# 9_LPDDR4_SDRAM1.net
KiCad netlist of a schematic drawn in Altium Designer
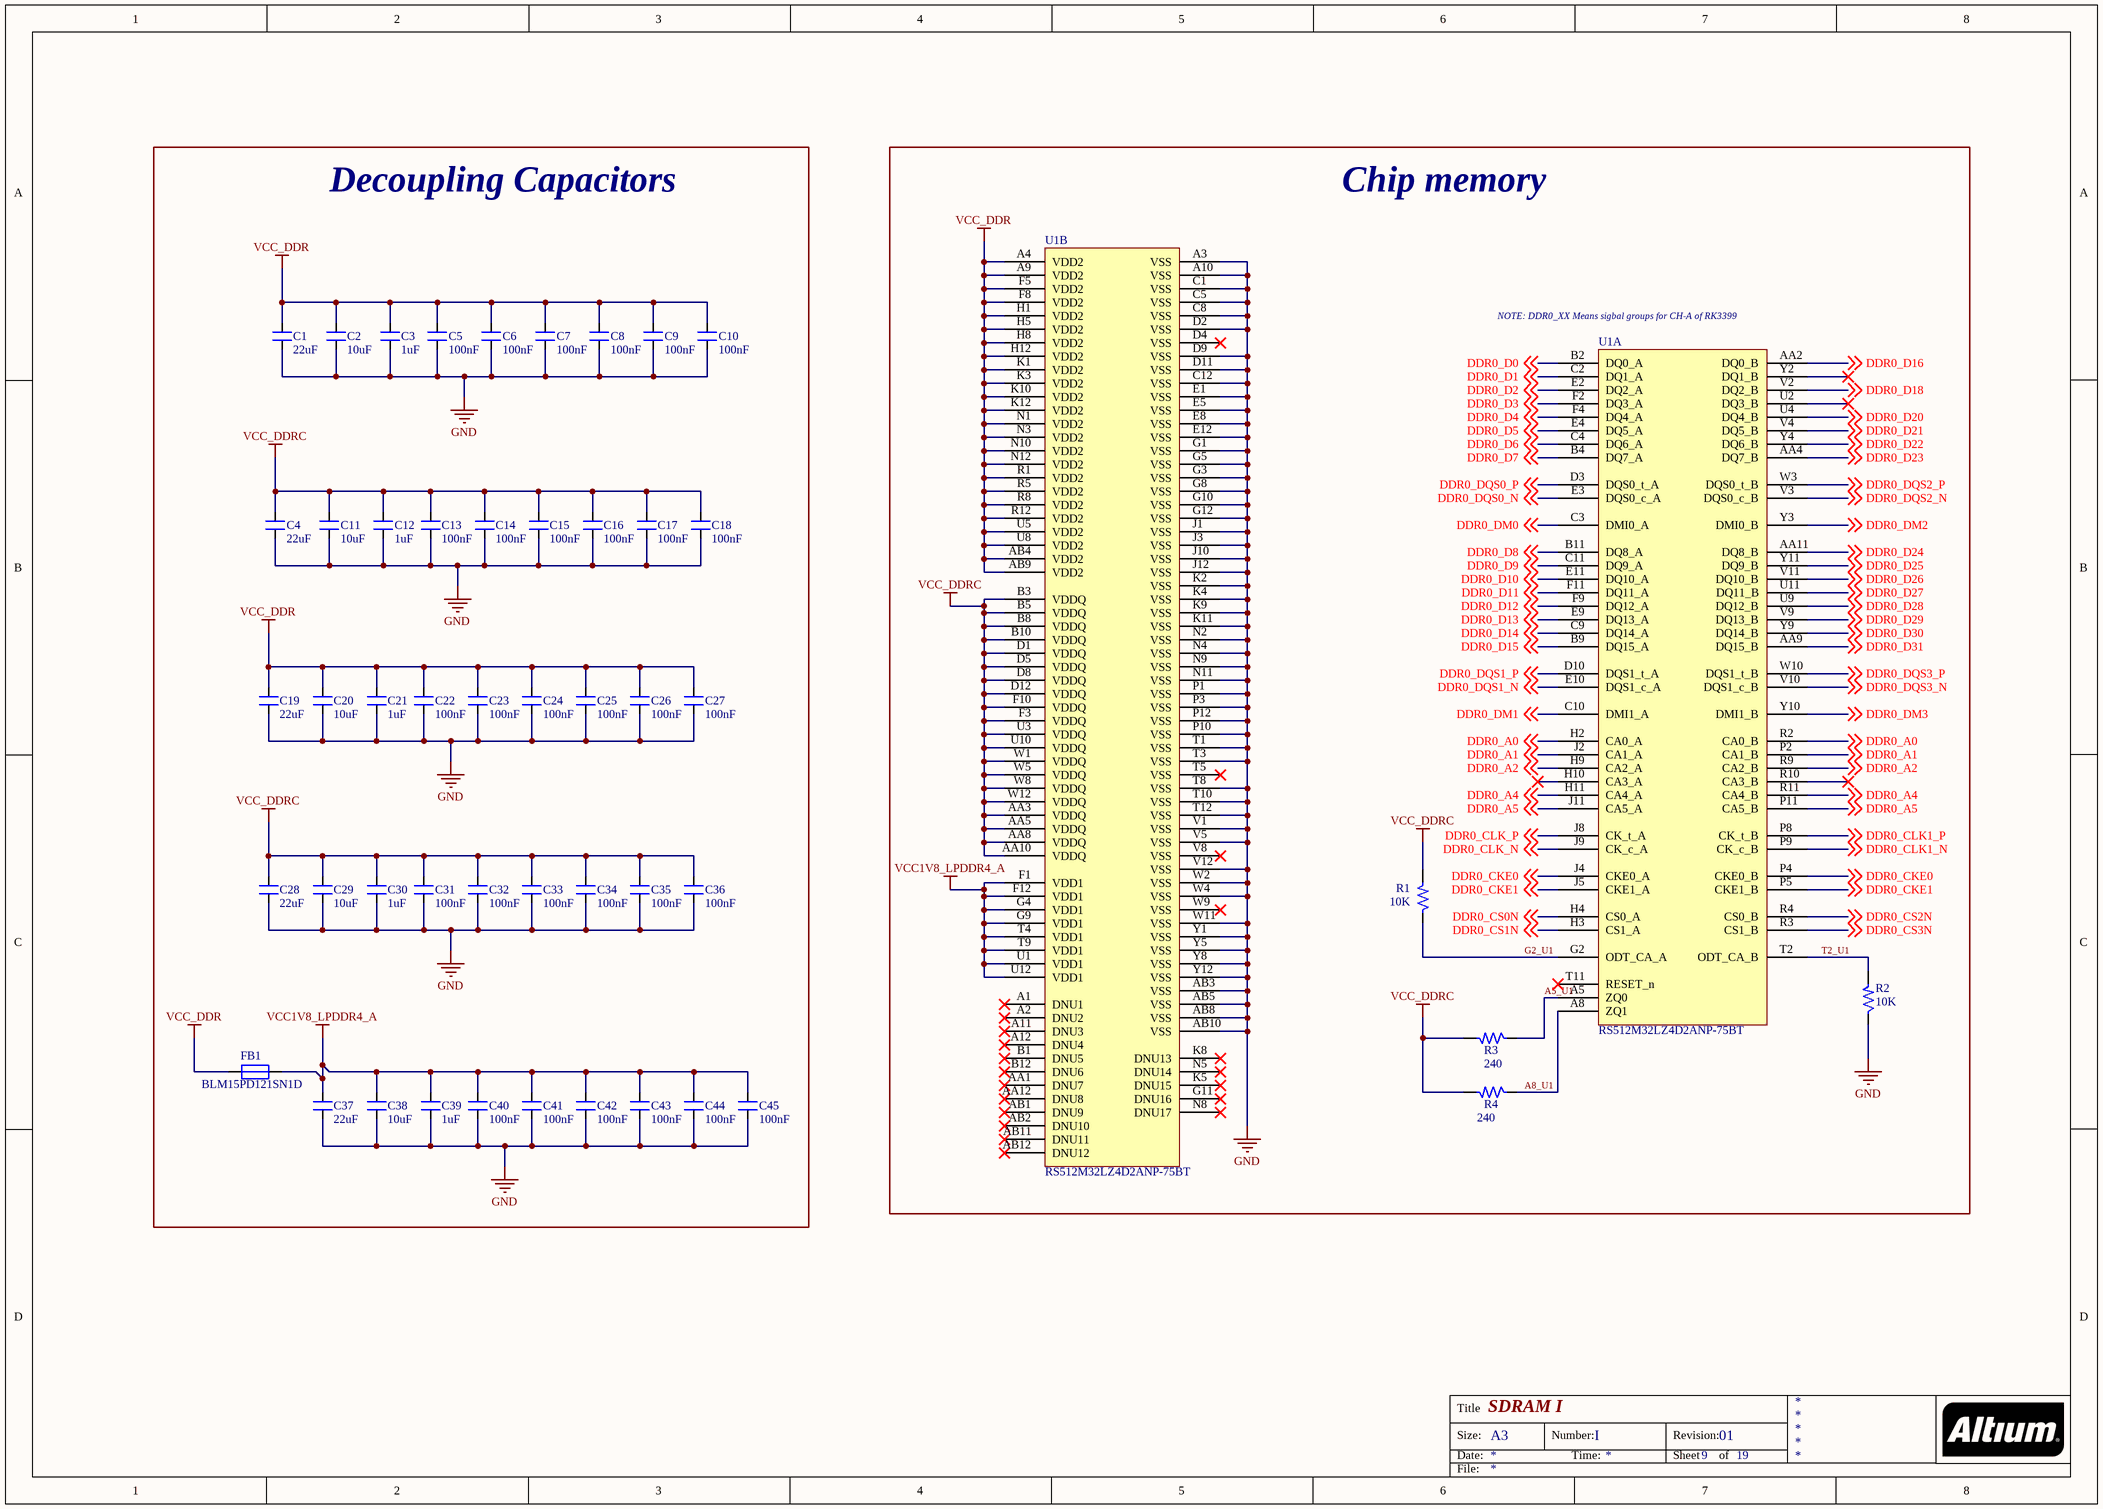
[diagram p0: [9] LPDDR4_SDRAM1.SchDoc]

(export (version "E")
  (design (tool "Eeschema 10.0.6"))
  (components
    (comp (ref "C1")
      (value "22uF")
      (footprint "CAP_0402")
      (description "22µF ±20% 6.3V Ceramic Capacitor X5R 0402 (1005 Metric)")
      (fields
        (field (name "MANUFACTURER") "Murata Electronics")
        (field (name "MANUFACTURER PART NUMBER") "CL05A226MQ5N6J8")
      )
      (libsource (lib "EsteemPCB_SOM_Course_intlib") (part "CAP_22uF-6.3V-20%-0402"))
    )
    (comp (ref "C2")
      (value "10uF")
      (footprint "CAP_0402")
      (description "10µF ±20% 10V Ceramic Capacitor X5R 0402 (1005 Metric)")
      (fields
        (field (name "MANUFACTURER PART NUMBER") "CL05A106MP5NUNC")
        (field (name "MANUFACTURER") "Samsung Electro-Mechanics")
      )
      (libsource (lib "EsteemPCB_SOM_Course_intlib") (part "CAP_10uF-10V-20%-0402"))
    )
    (comp (ref "C3")
      (value "1uF")
      (footprint "CAP_0201")
      (description "1µF ±20% 16V Ceramic Capacitor X5R 0201 (0603 Metric)")
      (fields
        (field (name "MANUFACTURER") "Samsung Electro-Mechanics")
        (field (name "MANUFACTURER PART NUMBER") "CL03A105MO3NRNH")
      )
      (libsource (lib "EsteemPCB_SOM_Course_intlib") (part "CAP_1uF-16V-10%-0201"))
    )
    (comp (ref "C4")
      (value "22uF")
      (footprint "CAP_0402")
      (description "22µF ±20% 6.3V Ceramic Capacitor X5R 0402 (1005 Metric)")
      (fields
        (field (name "MANUFACTURER") "Murata Electronics")
        (field (name "MANUFACTURER PART NUMBER") "CL05A226MQ5N6J8")
      )
      (libsource (lib "EsteemPCB_SOM_Course_intlib") (part "CAP_22uF-6.3V-20%-0402"))
    )
    (comp (ref "C5")
      (value "100nF")
      (footprint "CAP_0201")
      (description "0.1µF ±10% 25V Ceramic Capacitor X5R 0201 (0603 Metric)")
      (fields
        (field (name "MANUFACTURER") "TDK Corporation")
        (field (name "MANUFACTURER PART NUMBER") "C0603X5R1E104K030BB")
      )
      (libsource (lib "EsteemPCB_SOM_Course_intlib") (part "CAP_100nF-25V-10%-0201"))
    )
    (comp (ref "C6")
      (value "100nF")
      (footprint "CAP_0201")
      (description "0.1µF ±10% 25V Ceramic Capacitor X5R 0201 (0603 Metric)")
      (fields
        (field (name "MANUFACTURER") "TDK Corporation")
        (field (name "MANUFACTURER PART NUMBER") "C0603X5R1E104K030BB")
      )
      (libsource (lib "EsteemPCB_SOM_Course_intlib") (part "CAP_100nF-25V-10%-0201"))
    )
    (comp (ref "C7")
      (value "100nF")
      (footprint "CAP_0201")
      (description "0.1µF ±10% 25V Ceramic Capacitor X5R 0201 (0603 Metric)")
      (fields
        (field (name "MANUFACTURER") "TDK Corporation")
        (field (name "MANUFACTURER PART NUMBER") "C0603X5R1E104K030BB")
      )
      (libsource (lib "EsteemPCB_SOM_Course_intlib") (part "CAP_100nF-25V-10%-0201"))
    )
    (comp (ref "C8")
      (value "100nF")
      (footprint "CAP_0201")
      (description "0.1µF ±10% 25V Ceramic Capacitor X5R 0201 (0603 Metric)")
      (fields
        (field (name "MANUFACTURER") "TDK Corporation")
        (field (name "MANUFACTURER PART NUMBER") "C0603X5R1E104K030BB")
      )
      (libsource (lib "EsteemPCB_SOM_Course_intlib") (part "CAP_100nF-25V-10%-0201"))
    )
    (comp (ref "C9")
      (value "100nF")
      (footprint "CAP_0201")
      (description "0.1µF ±10% 25V Ceramic Capacitor X5R 0201 (0603 Metric)")
      (fields
        (field (name "MANUFACTURER") "TDK Corporation")
        (field (name "MANUFACTURER PART NUMBER") "C0603X5R1E104K030BB")
      )
      (libsource (lib "EsteemPCB_SOM_Course_intlib") (part "CAP_100nF-25V-10%-0201"))
    )
    (comp (ref "C10")
      (value "100nF")
      (footprint "CAP_0201")
      (description "0.1µF ±10% 25V Ceramic Capacitor X5R 0201 (0603 Metric)")
      (fields
        (field (name "MANUFACTURER") "TDK Corporation")
        (field (name "MANUFACTURER PART NUMBER") "C0603X5R1E104K030BB")
      )
      (libsource (lib "EsteemPCB_SOM_Course_intlib") (part "CAP_100nF-25V-10%-0201"))
    )
    (comp (ref "C11")
      (value "10uF")
      (footprint "CAP_0402")
      (description "10µF ±20% 10V Ceramic Capacitor X5R 0402 (1005 Metric)")
      (fields
        (field (name "MANUFACTURER PART NUMBER") "CL05A106MP5NUNC")
        (field (name "MANUFACTURER") "Samsung Electro-Mechanics")
      )
      (libsource (lib "EsteemPCB_SOM_Course_intlib") (part "CAP_10uF-10V-20%-0402"))
    )
    (comp (ref "C12")
      (value "1uF")
      (footprint "CAP_0201")
      (description "1µF ±20% 16V Ceramic Capacitor X5R 0201 (0603 Metric)")
      (fields
        (field (name "MANUFACTURER") "Samsung Electro-Mechanics")
        (field (name "MANUFACTURER PART NUMBER") "CL03A105MO3NRNH")
      )
      (libsource (lib "EsteemPCB_SOM_Course_intlib") (part "CAP_1uF-16V-10%-0201"))
    )
    (comp (ref "C13")
      (value "100nF")
      (footprint "CAP_0201")
      (description "0.1µF ±10% 25V Ceramic Capacitor X5R 0201 (0603 Metric)")
      (fields
        (field (name "MANUFACTURER") "TDK Corporation")
        (field (name "MANUFACTURER PART NUMBER") "C0603X5R1E104K030BB")
      )
      (libsource (lib "EsteemPCB_SOM_Course_intlib") (part "CAP_100nF-25V-10%-0201"))
    )
    (comp (ref "C14")
      (value "100nF")
      (footprint "CAP_0201")
      (description "0.1µF ±10% 25V Ceramic Capacitor X5R 0201 (0603 Metric)")
      (fields
        (field (name "MANUFACTURER") "TDK Corporation")
        (field (name "MANUFACTURER PART NUMBER") "C0603X5R1E104K030BB")
      )
      (libsource (lib "EsteemPCB_SOM_Course_intlib") (part "CAP_100nF-25V-10%-0201"))
    )
    (comp (ref "C15")
      (value "100nF")
      (footprint "CAP_0201")
      (description "0.1µF ±10% 25V Ceramic Capacitor X5R 0201 (0603 Metric)")
      (fields
        (field (name "MANUFACTURER") "TDK Corporation")
        (field (name "MANUFACTURER PART NUMBER") "C0603X5R1E104K030BB")
      )
      (libsource (lib "EsteemPCB_SOM_Course_intlib") (part "CAP_100nF-25V-10%-0201"))
    )
    (comp (ref "C16")
      (value "100nF")
      (footprint "CAP_0201")
      (description "0.1µF ±10% 25V Ceramic Capacitor X5R 0201 (0603 Metric)")
      (fields
        (field (name "MANUFACTURER") "TDK Corporation")
        (field (name "MANUFACTURER PART NUMBER") "C0603X5R1E104K030BB")
      )
      (libsource (lib "EsteemPCB_SOM_Course_intlib") (part "CAP_100nF-25V-10%-0201"))
    )
    (comp (ref "C17")
      (value "100nF")
      (footprint "CAP_0201")
      (description "0.1µF ±10% 25V Ceramic Capacitor X5R 0201 (0603 Metric)")
      (fields
        (field (name "MANUFACTURER") "TDK Corporation")
        (field (name "MANUFACTURER PART NUMBER") "C0603X5R1E104K030BB")
      )
      (libsource (lib "EsteemPCB_SOM_Course_intlib") (part "CAP_100nF-25V-10%-0201"))
    )
    (comp (ref "C18")
      (value "100nF")
      (footprint "CAP_0201")
      (description "0.1µF ±10% 25V Ceramic Capacitor X5R 0201 (0603 Metric)")
      (fields
        (field (name "MANUFACTURER") "TDK Corporation")
        (field (name "MANUFACTURER PART NUMBER") "C0603X5R1E104K030BB")
      )
      (libsource (lib "EsteemPCB_SOM_Course_intlib") (part "CAP_100nF-25V-10%-0201"))
    )
    (comp (ref "C19")
      (value "22uF")
      (footprint "CAP_0402")
      (description "22µF ±20% 6.3V Ceramic Capacitor X5R 0402 (1005 Metric)")
      (fields
        (field (name "MANUFACTURER") "Murata Electronics")
        (field (name "MANUFACTURER PART NUMBER") "CL05A226MQ5N6J8")
      )
      (libsource (lib "EsteemPCB_SOM_Course_intlib") (part "CAP_22uF-6.3V-20%-0402"))
    )
    (comp (ref "C20")
      (value "10uF")
      (footprint "CAP_0402")
      (description "10µF ±20% 10V Ceramic Capacitor X5R 0402 (1005 Metric)")
      (fields
        (field (name "MANUFACTURER PART NUMBER") "CL05A106MP5NUNC")
        (field (name "MANUFACTURER") "Samsung Electro-Mechanics")
      )
      (libsource (lib "EsteemPCB_SOM_Course_intlib") (part "CAP_10uF-10V-20%-0402"))
    )
    (comp (ref "C21")
      (value "1uF")
      (footprint "CAP_0201")
      (description "1µF ±20% 16V Ceramic Capacitor X5R 0201 (0603 Metric)")
      (fields
        (field (name "MANUFACTURER") "Samsung Electro-Mechanics")
        (field (name "MANUFACTURER PART NUMBER") "CL03A105MO3NRNH")
      )
      (libsource (lib "EsteemPCB_SOM_Course_intlib") (part "CAP_1uF-16V-10%-0201"))
    )
    (comp (ref "C22")
      (value "100nF")
      (footprint "CAP_0201")
      (description "0.1µF ±10% 25V Ceramic Capacitor X5R 0201 (0603 Metric)")
      (fields
        (field (name "MANUFACTURER") "TDK Corporation")
        (field (name "MANUFACTURER PART NUMBER") "C0603X5R1E104K030BB")
      )
      (libsource (lib "EsteemPCB_SOM_Course_intlib") (part "CAP_100nF-25V-10%-0201"))
    )
    (comp (ref "C23")
      (value "100nF")
      (footprint "CAP_0201")
      (description "0.1µF ±10% 25V Ceramic Capacitor X5R 0201 (0603 Metric)")
      (fields
        (field (name "MANUFACTURER") "TDK Corporation")
        (field (name "MANUFACTURER PART NUMBER") "C0603X5R1E104K030BB")
      )
      (libsource (lib "EsteemPCB_SOM_Course_intlib") (part "CAP_100nF-25V-10%-0201"))
    )
    (comp (ref "C24")
      (value "100nF")
      (footprint "CAP_0201")
      (description "0.1µF ±10% 25V Ceramic Capacitor X5R 0201 (0603 Metric)")
      (fields
        (field (name "MANUFACTURER") "TDK Corporation")
        (field (name "MANUFACTURER PART NUMBER") "C0603X5R1E104K030BB")
      )
      (libsource (lib "EsteemPCB_SOM_Course_intlib") (part "CAP_100nF-25V-10%-0201"))
    )
    (comp (ref "C25")
      (value "100nF")
      (footprint "CAP_0201")
      (description "0.1µF ±10% 25V Ceramic Capacitor X5R 0201 (0603 Metric)")
      (fields
        (field (name "MANUFACTURER") "TDK Corporation")
        (field (name "MANUFACTURER PART NUMBER") "C0603X5R1E104K030BB")
      )
      (libsource (lib "EsteemPCB_SOM_Course_intlib") (part "CAP_100nF-25V-10%-0201"))
    )
    (comp (ref "C26")
      (value "100nF")
      (footprint "CAP_0201")
      (description "0.1µF ±10% 25V Ceramic Capacitor X5R 0201 (0603 Metric)")
      (fields
        (field (name "MANUFACTURER") "TDK Corporation")
        (field (name "MANUFACTURER PART NUMBER") "C0603X5R1E104K030BB")
      )
      (libsource (lib "EsteemPCB_SOM_Course_intlib") (part "CAP_100nF-25V-10%-0201"))
    )
    (comp (ref "C27")
      (value "100nF")
      (footprint "CAP_0201")
      (description "0.1µF ±10% 25V Ceramic Capacitor X5R 0201 (0603 Metric)")
      (fields
        (field (name "MANUFACTURER") "TDK Corporation")
        (field (name "MANUFACTURER PART NUMBER") "C0603X5R1E104K030BB")
      )
      (libsource (lib "EsteemPCB_SOM_Course_intlib") (part "CAP_100nF-25V-10%-0201"))
    )
    (comp (ref "C28")
      (value "22uF")
      (footprint "CAP_0402")
      (description "22µF ±20% 6.3V Ceramic Capacitor X5R 0402 (1005 Metric)")
      (fields
        (field (name "MANUFACTURER") "Murata Electronics")
        (field (name "MANUFACTURER PART NUMBER") "CL05A226MQ5N6J8")
      )
      (libsource (lib "EsteemPCB_SOM_Course_intlib") (part "CAP_22uF-6.3V-20%-0402"))
    )
    (comp (ref "C29")
      (value "10uF")
      (footprint "CAP_0402")
      (description "10µF ±20% 10V Ceramic Capacitor X5R 0402 (1005 Metric)")
      (fields
        (field (name "MANUFACTURER PART NUMBER") "CL05A106MP5NUNC")
        (field (name "MANUFACTURER") "Samsung Electro-Mechanics")
      )
      (libsource (lib "EsteemPCB_SOM_Course_intlib") (part "CAP_10uF-10V-20%-0402"))
    )
    (comp (ref "C30")
      (value "1uF")
      (footprint "CAP_0201")
      (description "1µF ±20% 16V Ceramic Capacitor X5R 0201 (0603 Metric)")
      (fields
        (field (name "MANUFACTURER") "Samsung Electro-Mechanics")
        (field (name "MANUFACTURER PART NUMBER") "CL03A105MO3NRNH")
      )
      (libsource (lib "EsteemPCB_SOM_Course_intlib") (part "CAP_1uF-16V-10%-0201"))
    )
    (comp (ref "C31")
      (value "100nF")
      (footprint "CAP_0201")
      (description "0.1µF ±10% 25V Ceramic Capacitor X5R 0201 (0603 Metric)")
      (fields
        (field (name "MANUFACTURER") "TDK Corporation")
        (field (name "MANUFACTURER PART NUMBER") "C0603X5R1E104K030BB")
      )
      (libsource (lib "EsteemPCB_SOM_Course_intlib") (part "CAP_100nF-25V-10%-0201"))
    )
    (comp (ref "C32")
      (value "100nF")
      (footprint "CAP_0201")
      (description "0.1µF ±10% 25V Ceramic Capacitor X5R 0201 (0603 Metric)")
      (fields
        (field (name "MANUFACTURER") "TDK Corporation")
        (field (name "MANUFACTURER PART NUMBER") "C0603X5R1E104K030BB")
      )
      (libsource (lib "EsteemPCB_SOM_Course_intlib") (part "CAP_100nF-25V-10%-0201"))
    )
    (comp (ref "C33")
      (value "100nF")
      (footprint "CAP_0201")
      (description "0.1µF ±10% 25V Ceramic Capacitor X5R 0201 (0603 Metric)")
      (fields
        (field (name "MANUFACTURER") "TDK Corporation")
        (field (name "MANUFACTURER PART NUMBER") "C0603X5R1E104K030BB")
      )
      (libsource (lib "EsteemPCB_SOM_Course_intlib") (part "CAP_100nF-25V-10%-0201"))
    )
    (comp (ref "C34")
      (value "100nF")
      (footprint "CAP_0201")
      (description "0.1µF ±10% 25V Ceramic Capacitor X5R 0201 (0603 Metric)")
      (fields
        (field (name "MANUFACTURER") "TDK Corporation")
        (field (name "MANUFACTURER PART NUMBER") "C0603X5R1E104K030BB")
      )
      (libsource (lib "EsteemPCB_SOM_Course_intlib") (part "CAP_100nF-25V-10%-0201"))
    )
    (comp (ref "C35")
      (value "100nF")
      (footprint "CAP_0201")
      (description "0.1µF ±10% 25V Ceramic Capacitor X5R 0201 (0603 Metric)")
      (fields
        (field (name "MANUFACTURER") "TDK Corporation")
        (field (name "MANUFACTURER PART NUMBER") "C0603X5R1E104K030BB")
      )
      (libsource (lib "EsteemPCB_SOM_Course_intlib") (part "CAP_100nF-25V-10%-0201"))
    )
    (comp (ref "C36")
      (value "100nF")
      (footprint "CAP_0201")
      (description "0.1µF ±10% 25V Ceramic Capacitor X5R 0201 (0603 Metric)")
      (fields
        (field (name "MANUFACTURER") "TDK Corporation")
        (field (name "MANUFACTURER PART NUMBER") "C0603X5R1E104K030BB")
      )
      (libsource (lib "EsteemPCB_SOM_Course_intlib") (part "CAP_100nF-25V-10%-0201"))
    )
    (comp (ref "C37")
      (value "22uF")
      (footprint "CAP_0402")
      (description "22µF ±20% 6.3V Ceramic Capacitor X5R 0402 (1005 Metric)")
      (fields
        (field (name "MANUFACTURER") "Murata Electronics")
        (field (name "MANUFACTURER PART NUMBER") "CL05A226MQ5N6J8")
      )
      (libsource (lib "EsteemPCB_SOM_Course_intlib") (part "CAP_22uF-6.3V-20%-0402"))
    )
    (comp (ref "C38")
      (value "10uF")
      (footprint "CAP_0402")
      (description "10µF ±20% 10V Ceramic Capacitor X5R 0402 (1005 Metric)")
      (fields
        (field (name "MANUFACTURER PART NUMBER") "CL05A106MP5NUNC")
        (field (name "MANUFACTURER") "Samsung Electro-Mechanics")
      )
      (libsource (lib "EsteemPCB_SOM_Course_intlib") (part "CAP_10uF-10V-20%-0402"))
    )
    (comp (ref "C39")
      (value "1uF")
      (footprint "CAP_0201")
      (description "1µF ±20% 16V Ceramic Capacitor X5R 0201 (0603 Metric)")
      (fields
        (field (name "MANUFACTURER") "Samsung Electro-Mechanics")
        (field (name "MANUFACTURER PART NUMBER") "CL03A105MO3NRNH")
      )
      (libsource (lib "EsteemPCB_SOM_Course_intlib") (part "CAP_1uF-16V-10%-0201"))
    )
    (comp (ref "C40")
      (value "100nF")
      (footprint "CAP_0201")
      (description "0.1µF ±10% 25V Ceramic Capacitor X5R 0201 (0603 Metric)")
      (fields
        (field (name "MANUFACTURER") "TDK Corporation")
        (field (name "MANUFACTURER PART NUMBER") "C0603X5R1E104K030BB")
      )
      (libsource (lib "EsteemPCB_SOM_Course_intlib") (part "CAP_100nF-25V-10%-0201"))
    )
    (comp (ref "C41")
      (value "100nF")
      (footprint "CAP_0201")
      (description "0.1µF ±10% 25V Ceramic Capacitor X5R 0201 (0603 Metric)")
      (fields
        (field (name "MANUFACTURER") "TDK Corporation")
        (field (name "MANUFACTURER PART NUMBER") "C0603X5R1E104K030BB")
      )
      (libsource (lib "EsteemPCB_SOM_Course_intlib") (part "CAP_100nF-25V-10%-0201"))
    )
    (comp (ref "C42")
      (value "100nF")
      (footprint "CAP_0201")
      (description "0.1µF ±10% 25V Ceramic Capacitor X5R 0201 (0603 Metric)")
      (fields
        (field (name "MANUFACTURER") "TDK Corporation")
        (field (name "MANUFACTURER PART NUMBER") "C0603X5R1E104K030BB")
      )
      (libsource (lib "EsteemPCB_SOM_Course_intlib") (part "CAP_100nF-25V-10%-0201"))
    )
    (comp (ref "C43")
      (value "100nF")
      (footprint "CAP_0201")
      (description "0.1µF ±10% 25V Ceramic Capacitor X5R 0201 (0603 Metric)")
      (fields
        (field (name "MANUFACTURER") "TDK Corporation")
        (field (name "MANUFACTURER PART NUMBER") "C0603X5R1E104K030BB")
      )
      (libsource (lib "EsteemPCB_SOM_Course_intlib") (part "CAP_100nF-25V-10%-0201"))
    )
    (comp (ref "C44")
      (value "100nF")
      (footprint "CAP_0201")
      (description "0.1µF ±10% 25V Ceramic Capacitor X5R 0201 (0603 Metric)")
      (fields
        (field (name "MANUFACTURER") "TDK Corporation")
        (field (name "MANUFACTURER PART NUMBER") "C0603X5R1E104K030BB")
      )
      (libsource (lib "EsteemPCB_SOM_Course_intlib") (part "CAP_100nF-25V-10%-0201"))
    )
    (comp (ref "C45")
      (value "100nF")
      (footprint "CAP_0201")
      (description "0.1µF ±10% 25V Ceramic Capacitor X5R 0201 (0603 Metric)")
      (fields
        (field (name "MANUFACTURER") "TDK Corporation")
        (field (name "MANUFACTURER PART NUMBER") "C0603X5R1E104K030BB")
      )
      (libsource (lib "EsteemPCB_SOM_Course_intlib") (part "CAP_100nF-25V-10%-0201"))
    )
    (comp (ref "FB1")
      (value "BLM15PD121SN1D")
      (footprint "RES_0402")
      (description "120 Ohms @ 100MHz 1 Power Line Ferrite Bead 0402 (1005 Metric) 1.3A 90mOhm")
      (fields (field (name "MANUFACTURER") "Murata Electronics"))
      (libsource (lib "EsteemPCB_SOM_Course_intlib") (part "FB_120R-1.3A-100Mhz-0402"))
    )
    (comp (ref "R1")
      (value "10K")
      (footprint "RES_0201")
      (description "10 kOhms ±1% 0.05W, 1/20W Chip Resistor 0201 (0603 Metric) Thick Film")
      (fields
        (field (name "MANUFACTURER") "Stackpole Electronics Inc")
        (field (name "MANUFACTURER PART NUMBER") "RMCF0201FT10K0")
      )
      (libsource (lib "EsteemPCB_SOM_Course_intlib") (part "RES_10K-0.05W-1%-0201"))
    )
    (comp (ref "R2")
      (value "10K")
      (footprint "RES_0201")
      (description "10 kOhms ±1% 0.05W, 1/20W Chip Resistor 0201 (0603 Metric) Thick Film")
      (fields
        (field (name "MANUFACTURER") "Stackpole Electronics Inc")
        (field (name "MANUFACTURER PART NUMBER") "RMCF0201FT10K0")
      )
      (libsource (lib "EsteemPCB_SOM_Course_intlib") (part "RES_10K-0.05W-1%-0201"))
    )
    (comp (ref "R3")
      (value "240")
      (footprint "RES_0201")
      (description "10 kOhms ±1% 0.05W, 1/20W Chip Resistor 0201 (0603 Metric) Thick Film")
      (fields
        (field (name "MANUFACTURER") "Stackpole Electronics Inc")
        (field (name "MANUFACTURER PART NUMBER") "RMCF0201FT10K0")
      )
      (libsource (lib "EsteemPCB_SOM_Course_intlib") (part "RES_10K-0.05W-1%-0201"))
    )
    (comp (ref "R4")
      (value "240")
      (footprint "RES_0201")
      (description "10 kOhms ±1% 0.05W, 1/20W Chip Resistor 0201 (0603 Metric) Thick Film")
      (fields
        (field (name "MANUFACTURER") "Stackpole Electronics Inc")
        (field (name "MANUFACTURER PART NUMBER") "RMCF0201FT10K0")
      )
      (libsource (lib "EsteemPCB_SOM_Course_intlib") (part "RES_10K-0.05W-1%-0201"))
    )
    (comp (ref "U1")
      (value "RS512M32LZ4D2ANP-75BT")
      (footprint "FBGA200_SMD")
      (fields (field (name "MANUFACTURER") "RAYSON"))
      (libsource (lib "EsteemPCB_SOM_Course_intlib") (part "IC_RS512M32LZ4D2ANP-75BT"))
    )
  )
  (nets
    (net (code "1") (name "/A5_U1") (class "Default")
      (node (ref "R3") (pin "1") (pinfunction "1_1") (pintype "passive"))
      (node (ref "U1") (pin "A5") (pinfunction "ZQ0_A5") (pintype "passive"))
    )
    (net (code "2") (name "/A8_U1") (class "Default")
      (node (ref "R4") (pin "1") (pinfunction "1_1") (pintype "passive"))
      (node (ref "U1") (pin "A8") (pinfunction "ZQ1_A8") (pintype "passive"))
    )
    (net (code "3") (name "/G2_U1") (class "Default")
      (node (ref "R1") (pin "1") (pinfunction "1_1") (pintype "passive"))
      (node (ref "U1") (pin "G2") (pinfunction "ODT_CA_A_G2") (pintype "passive"))
    )
    (net (code "4") (name "/T2_U1") (class "Default")
      (node (ref "R2") (pin "2") (pinfunction "2_2") (pintype "passive"))
      (node (ref "U1") (pin "T2") (pinfunction "ODT_CA_B_T2") (pintype "passive"))
    )
    (net (code "5") (name "DDR0_A0") (class "Default")
      (node (ref "U1") (pin "H2") (pinfunction "CA0_A_H2") (pintype "passive"))
      (node (ref "U1") (pin "R2") (pinfunction "CA0_B_R2") (pintype "passive"))
    )
    (net (code "6") (name "DDR0_A1") (class "Default")
      (node (ref "U1") (pin "J2") (pinfunction "CA1_A_J2") (pintype "passive"))
      (node (ref "U1") (pin "P2") (pinfunction "CA1_B_P2") (pintype "passive"))
    )
    (net (code "7") (name "DDR0_A2") (class "Default")
      (node (ref "U1") (pin "H9") (pinfunction "CA2_A_H9") (pintype "passive"))
      (node (ref "U1") (pin "R9") (pinfunction "CA2_B_R9") (pintype "passive"))
    )
    (net (code "8") (name "DDR0_A4") (class "Default")
      (node (ref "U1") (pin "H11") (pinfunction "CA4_A_H11") (pintype "passive"))
      (node (ref "U1") (pin "R11") (pinfunction "CA4_B_R11") (pintype "passive"))
    )
    (net (code "9") (name "DDR0_A5") (class "Default")
      (node (ref "U1") (pin "J11") (pinfunction "CA5_A_J11") (pintype "passive"))
      (node (ref "U1") (pin "P11") (pinfunction "CA5_B_P11") (pintype "passive"))
    )
    (net (code "10") (name "DDR0_CKE0") (class "Default")
      (node (ref "U1") (pin "J4") (pinfunction "CKE0_A_J4") (pintype "passive"))
      (node (ref "U1") (pin "P4") (pinfunction "CKE0_B_P4") (pintype "passive"))
    )
    (net (code "11") (name "DDR0_CKE1") (class "Default")
      (node (ref "U1") (pin "J5") (pinfunction "CKE1_A_J5") (pintype "passive"))
      (node (ref "U1") (pin "P5") (pinfunction "CKE1_B_P5") (pintype "passive"))
    )
    (net (code "12") (name "DDR0_CLK1_N") (class "Default")
      (node (ref "U1") (pin "P9") (pinfunction "CK_c_B_P9") (pintype "passive"))
    )
    (net (code "13") (name "DDR0_CLK1_P") (class "Default")
      (node (ref "U1") (pin "P8") (pinfunction "CK_t_B_P8") (pintype "passive"))
    )
    (net (code "14") (name "DDR0_CLK_N") (class "Default")
      (node (ref "U1") (pin "J9") (pinfunction "CK_c_A_J9") (pintype "passive"))
    )
    (net (code "15") (name "DDR0_CLK_P") (class "Default")
      (node (ref "U1") (pin "J8") (pinfunction "CK_t_A_J8") (pintype "passive"))
    )
    (net (code "16") (name "DDR0_CS0N") (class "Default")
      (node (ref "U1") (pin "H4") (pinfunction "CS0_A_H4") (pintype "passive"))
    )
    (net (code "17") (name "DDR0_CS1N") (class "Default")
      (node (ref "U1") (pin "H3") (pinfunction "CS1_A_H3") (pintype "passive"))
    )
    (net (code "18") (name "DDR0_CS2N") (class "Default")
      (node (ref "U1") (pin "R4") (pinfunction "CS0_B_R4") (pintype "passive"))
    )
    (net (code "19") (name "DDR0_CS3N") (class "Default")
      (node (ref "U1") (pin "R3") (pinfunction "CS1_B_R3") (pintype "passive"))
    )
    (net (code "20") (name "DDR0_D0") (class "Default")
      (node (ref "U1") (pin "B2") (pinfunction "DQ0_A_B2") (pintype "passive"))
    )
    (net (code "21") (name "DDR0_D1") (class "Default")
      (node (ref "U1") (pin "C2") (pinfunction "DQ1_A_C2") (pintype "passive"))
    )
    (net (code "22") (name "DDR0_D2") (class "Default")
      (node (ref "U1") (pin "E2") (pinfunction "DQ2_A_E2") (pintype "passive"))
    )
    (net (code "23") (name "DDR0_D3") (class "Default")
      (node (ref "U1") (pin "F2") (pinfunction "DQ3_A_F2") (pintype "passive"))
    )
    (net (code "24") (name "DDR0_D4") (class "Default")
      (node (ref "U1") (pin "F4") (pinfunction "DQ4_A_F4") (pintype "passive"))
    )
    (net (code "25") (name "DDR0_D5") (class "Default")
      (node (ref "U1") (pin "E4") (pinfunction "DQ5_A_E4") (pintype "passive"))
    )
    (net (code "26") (name "DDR0_D6") (class "Default")
      (node (ref "U1") (pin "C4") (pinfunction "DQ6_A_C4") (pintype "passive"))
    )
    (net (code "27") (name "DDR0_D7") (class "Default")
      (node (ref "U1") (pin "B4") (pinfunction "DQ7_A_B4") (pintype "passive"))
    )
    (net (code "28") (name "DDR0_D8") (class "Default")
      (node (ref "U1") (pin "B11") (pinfunction "DQ8_A_B11") (pintype "passive"))
    )
    (net (code "29") (name "DDR0_D9") (class "Default")
      (node (ref "U1") (pin "C11") (pinfunction "DQ9_A_C11") (pintype "passive"))
    )
    (net (code "30") (name "DDR0_D10") (class "Default")
      (node (ref "U1") (pin "E11") (pinfunction "DQ10_A_E11") (pintype "passive"))
    )
    (net (code "31") (name "DDR0_D11") (class "Default")
      (node (ref "U1") (pin "F11") (pinfunction "DQ11_A_F11") (pintype "passive"))
    )
    (net (code "32") (name "DDR0_D12") (class "Default")
      (node (ref "U1") (pin "F9") (pinfunction "DQ12_A_F9") (pintype "passive"))
    )
    (net (code "33") (name "DDR0_D13") (class "Default")
      (node (ref "U1") (pin "E9") (pinfunction "DQ13_A_E9") (pintype "passive"))
    )
    (net (code "34") (name "DDR0_D14") (class "Default")
      (node (ref "U1") (pin "C9") (pinfunction "DQ14_A_C9") (pintype "passive"))
    )
    (net (code "35") (name "DDR0_D15") (class "Default")
      (node (ref "U1") (pin "B9") (pinfunction "DQ15_A_B9") (pintype "passive"))
    )
    (net (code "36") (name "DDR0_D16") (class "Default")
      (node (ref "U1") (pin "AA2") (pinfunction "DQ0_B_AA2") (pintype "passive"))
    )
    (net (code "37") (name "DDR0_D18") (class "Default")
      (node (ref "U1") (pin "V2") (pinfunction "DQ2_B_V2") (pintype "passive"))
    )
    (net (code "38") (name "DDR0_D20") (class "Default")
      (node (ref "U1") (pin "U4") (pinfunction "DQ4_B_U4") (pintype "passive"))
    )
    (net (code "39") (name "DDR0_D21") (class "Default")
      (node (ref "U1") (pin "V4") (pinfunction "DQ5_B_V4") (pintype "passive"))
    )
    (net (code "40") (name "DDR0_D22") (class "Default")
      (node (ref "U1") (pin "Y4") (pinfunction "DQ6_B_Y4") (pintype "passive"))
    )
    (net (code "41") (name "DDR0_D23") (class "Default")
      (node (ref "U1") (pin "AA4") (pinfunction "DQ7_B_AA4") (pintype "passive"))
    )
    (net (code "42") (name "DDR0_D24") (class "Default")
      (node (ref "U1") (pin "AA11") (pinfunction "DQ8_B_AA11") (pintype "passive"))
    )
    (net (code "43") (name "DDR0_D25") (class "Default")
      (node (ref "U1") (pin "Y11") (pinfunction "DQ9_B_Y11") (pintype "passive"))
    )
    (net (code "44") (name "DDR0_D26") (class "Default")
      (node (ref "U1") (pin "V11") (pinfunction "DQ10_B_V11") (pintype "passive"))
    )
    (net (code "45") (name "DDR0_D27") (class "Default")
      (node (ref "U1") (pin "U11") (pinfunction "DQ11_B_U11") (pintype "passive"))
    )
    (net (code "46") (name "DDR0_D28") (class "Default")
      (node (ref "U1") (pin "U9") (pinfunction "DQ12_B_U9") (pintype "passive"))
    )
    (net (code "47") (name "DDR0_D29") (class "Default")
      (node (ref "U1") (pin "V9") (pinfunction "DQ13_B_V9") (pintype "passive"))
    )
    (net (code "48") (name "DDR0_D30") (class "Default")
      (node (ref "U1") (pin "Y9") (pinfunction "DQ14_B_Y9") (pintype "passive"))
    )
    (net (code "49") (name "DDR0_D31") (class "Default")
      (node (ref "U1") (pin "AA9") (pinfunction "DQ15_B_AA9") (pintype "passive"))
    )
    (net (code "50") (name "DDR0_DM0") (class "Default")
      (node (ref "U1") (pin "C3") (pinfunction "DMI0_A_C3") (pintype "passive"))
    )
    (net (code "51") (name "DDR0_DM1") (class "Default")
      (node (ref "U1") (pin "C10") (pinfunction "DMI1_A_C10") (pintype "passive"))
    )
    (net (code "52") (name "DDR0_DM2") (class "Default")
      (node (ref "U1") (pin "Y3") (pinfunction "DMI0_B_Y3") (pintype "passive"))
    )
    (net (code "53") (name "DDR0_DM3") (class "Default")
      (node (ref "U1") (pin "Y10") (pinfunction "DMI1_B_Y10") (pintype "passive"))
    )
    (net (code "54") (name "DDR0_DQS0_N") (class "Default")
      (node (ref "U1") (pin "E3") (pinfunction "DQS0_c_A_E3") (pintype "passive"))
    )
    (net (code "55") (name "DDR0_DQS0_P") (class "Default")
      (node (ref "U1") (pin "D3") (pinfunction "DQS0_t_A_D3") (pintype "passive"))
    )
    (net (code "56") (name "DDR0_DQS1_N") (class "Default")
      (node (ref "U1") (pin "E10") (pinfunction "DQS1_c_A_E10") (pintype "passive"))
    )
    (net (code "57") (name "DDR0_DQS1_P") (class "Default")
      (node (ref "U1") (pin "D10") (pinfunction "DQS1_t_A_D10") (pintype "passive"))
    )
    (net (code "58") (name "DDR0_DQS2_N") (class "Default")
      (node (ref "U1") (pin "V3") (pinfunction "DQS0_c_B_V3") (pintype "passive"))
    )
    (net (code "59") (name "DDR0_DQS2_P") (class "Default")
      (node (ref "U1") (pin "W3") (pinfunction "DQS0_t_B_W3") (pintype "passive"))
    )
    (net (code "60") (name "DDR0_DQS3_N") (class "Default")
      (node (ref "U1") (pin "V10") (pinfunction "DQS1_c_B_V10") (pintype "passive"))
    )
    (net (code "61") (name "DDR0_DQS3_P") (class "Default")
      (node (ref "U1") (pin "W10") (pinfunction "DQS1_t_B_W10") (pintype "passive"))
    )
    (net (code "62") (name "GND") (class "Default")
      (node (ref "C1") (pin "1") (pinfunction "1_1") (pintype "passive"))
      (node (ref "C10") (pin "1") (pinfunction "1_1") (pintype "passive"))
      (node (ref "C11") (pin "1") (pinfunction "1_1") (pintype "passive"))
      (node (ref "C12") (pin "1") (pinfunction "1_1") (pintype "passive"))
      (node (ref "C13") (pin "1") (pinfunction "1_1") (pintype "passive"))
      (node (ref "C14") (pin "1") (pinfunction "1_1") (pintype "passive"))
      (node (ref "C15") (pin "1") (pinfunction "1_1") (pintype "passive"))
      (node (ref "C16") (pin "1") (pinfunction "1_1") (pintype "passive"))
      (node (ref "C17") (pin "1") (pinfunction "1_1") (pintype "passive"))
      (node (ref "C18") (pin "1") (pinfunction "1_1") (pintype "passive"))
      (node (ref "C19") (pin "1") (pinfunction "1_1") (pintype "passive"))
      (node (ref "C2") (pin "1") (pinfunction "1_1") (pintype "passive"))
      (node (ref "C20") (pin "1") (pinfunction "1_1") (pintype "passive"))
      (node (ref "C21") (pin "1") (pinfunction "1_1") (pintype "passive"))
      (node (ref "C22") (pin "1") (pinfunction "1_1") (pintype "passive"))
      (node (ref "C23") (pin "1") (pinfunction "1_1") (pintype "passive"))
      (node (ref "C24") (pin "1") (pinfunction "1_1") (pintype "passive"))
      (node (ref "C25") (pin "1") (pinfunction "1_1") (pintype "passive"))
      (node (ref "C26") (pin "1") (pinfunction "1_1") (pintype "passive"))
      (node (ref "C27") (pin "1") (pinfunction "1_1") (pintype "passive"))
      (node (ref "C28") (pin "1") (pinfunction "1_1") (pintype "passive"))
      (node (ref "C29") (pin "1") (pinfunction "1_1") (pintype "passive"))
      (node (ref "C3") (pin "1") (pinfunction "1_1") (pintype "passive"))
      (node (ref "C30") (pin "1") (pinfunction "1_1") (pintype "passive"))
      (node (ref "C31") (pin "1") (pinfunction "1_1") (pintype "passive"))
      (node (ref "C32") (pin "1") (pinfunction "1_1") (pintype "passive"))
      (node (ref "C33") (pin "1") (pinfunction "1_1") (pintype "passive"))
      (node (ref "C34") (pin "1") (pinfunction "1_1") (pintype "passive"))
      (node (ref "C35") (pin "1") (pinfunction "1_1") (pintype "passive"))
      (node (ref "C36") (pin "1") (pinfunction "1_1") (pintype "passive"))
      (node (ref "C37") (pin "1") (pinfunction "1_1") (pintype "passive"))
      (node (ref "C38") (pin "1") (pinfunction "1_1") (pintype "passive"))
      (node (ref "C39") (pin "1") (pinfunction "1_1") (pintype "passive"))
      (node (ref "C4") (pin "1") (pinfunction "1_1") (pintype "passive"))
      (node (ref "C40") (pin "1") (pinfunction "1_1") (pintype "passive"))
      (node (ref "C41") (pin "1") (pinfunction "1_1") (pintype "passive"))
      (node (ref "C42") (pin "1") (pinfunction "1_1") (pintype "passive"))
      (node (ref "C43") (pin "1") (pinfunction "1_1") (pintype "passive"))
      (node (ref "C44") (pin "1") (pinfunction "1_1") (pintype "passive"))
      (node (ref "C45") (pin "1") (pinfunction "1_1") (pintype "passive"))
      (node (ref "C5") (pin "1") (pinfunction "1_1") (pintype "passive"))
      (node (ref "C6") (pin "1") (pinfunction "1_1") (pintype "passive"))
      (node (ref "C7") (pin "1") (pinfunction "1_1") (pintype "passive"))
      (node (ref "C8") (pin "1") (pinfunction "1_1") (pintype "passive"))
      (node (ref "C9") (pin "1") (pinfunction "1_1") (pintype "passive"))
      (node (ref "R2") (pin "1") (pinfunction "1_1") (pintype "passive"))
      (node (ref "U1") (pin "A10") (pinfunction "VSS_A10") (pintype "passive"))
      (node (ref "U1") (pin "A3") (pinfunction "VSS_A3") (pintype "passive"))
      (node (ref "U1") (pin "AB10") (pinfunction "VSS_AB10") (pintype "passive"))
      (node (ref "U1") (pin "AB3") (pinfunction "VSS_AB3") (pintype "passive"))
      (node (ref "U1") (pin "AB5") (pinfunction "VSS_AB5") (pintype "passive"))
      (node (ref "U1") (pin "AB8") (pinfunction "VSS_AB8") (pintype "passive"))
      (node (ref "U1") (pin "C1") (pinfunction "VSS_C1") (pintype "passive"))
      (node (ref "U1") (pin "C12") (pinfunction "VSS_C12") (pintype "passive"))
      (node (ref "U1") (pin "C5") (pinfunction "VSS_C5") (pintype "passive"))
      (node (ref "U1") (pin "C8") (pinfunction "VSS_C8") (pintype "passive"))
      (node (ref "U1") (pin "D11") (pinfunction "VSS_D11") (pintype "passive"))
      (node (ref "U1") (pin "D2") (pinfunction "VSS_D2") (pintype "passive"))
      (node (ref "U1") (pin "D9") (pinfunction "VSS_D9") (pintype "passive"))
      (node (ref "U1") (pin "E1") (pinfunction "VSS_E1") (pintype "passive"))
      (node (ref "U1") (pin "E12") (pinfunction "VSS_E12") (pintype "passive"))
      (node (ref "U1") (pin "E5") (pinfunction "VSS_E5") (pintype "passive"))
      (node (ref "U1") (pin "E8") (pinfunction "VSS_E8") (pintype "passive"))
      (node (ref "U1") (pin "G1") (pinfunction "VSS_G1") (pintype "passive"))
      (node (ref "U1") (pin "G10") (pinfunction "VSS_G10") (pintype "passive"))
      (node (ref "U1") (pin "G12") (pinfunction "VSS_G12") (pintype "passive"))
      (node (ref "U1") (pin "G3") (pinfunction "VSS_G3") (pintype "passive"))
      (node (ref "U1") (pin "G5") (pinfunction "VSS_G5") (pintype "passive"))
      (node (ref "U1") (pin "G8") (pinfunction "VSS_G8") (pintype "passive"))
      (node (ref "U1") (pin "J1") (pinfunction "VSS_J1") (pintype "passive"))
      (node (ref "U1") (pin "J10") (pinfunction "VSS_J10") (pintype "passive"))
      (node (ref "U1") (pin "J12") (pinfunction "VSS_J12") (pintype "passive"))
      (node (ref "U1") (pin "J3") (pinfunction "VSS_J3") (pintype "passive"))
      (node (ref "U1") (pin "K11") (pinfunction "VSS_K11") (pintype "passive"))
      (node (ref "U1") (pin "K2") (pinfunction "VSS_K2") (pintype "passive"))
      (node (ref "U1") (pin "K4") (pinfunction "VSS_K4") (pintype "passive"))
      (node (ref "U1") (pin "K9") (pinfunction "VSS_K9") (pintype "passive"))
      (node (ref "U1") (pin "N11") (pinfunction "VSS_N11") (pintype "passive"))
      (node (ref "U1") (pin "N2") (pinfunction "VSS_N2") (pintype "passive"))
      (node (ref "U1") (pin "N4") (pinfunction "VSS_N4") (pintype "passive"))
      (node (ref "U1") (pin "N9") (pinfunction "VSS_N9") (pintype "passive"))
      (node (ref "U1") (pin "P1") (pinfunction "VSS_P1") (pintype "passive"))
      (node (ref "U1") (pin "P10") (pinfunction "VSS_P10") (pintype "passive"))
      (node (ref "U1") (pin "P12") (pinfunction "VSS_P12") (pintype "passive"))
      (node (ref "U1") (pin "P3") (pinfunction "VSS_P3") (pintype "passive"))
      (node (ref "U1") (pin "T1") (pinfunction "VSS_T1") (pintype "passive"))
      (node (ref "U1") (pin "T10") (pinfunction "VSS_T10") (pintype "passive"))
      (node (ref "U1") (pin "T12") (pinfunction "VSS_T12") (pintype "passive"))
      (node (ref "U1") (pin "T3") (pinfunction "VSS_T3") (pintype "passive"))
      (node (ref "U1") (pin "T8") (pinfunction "VSS_T8") (pintype "passive"))
      (node (ref "U1") (pin "V1") (pinfunction "VSS_V1") (pintype "passive"))
      (node (ref "U1") (pin "V12") (pinfunction "VSS_V12") (pintype "passive"))
      (node (ref "U1") (pin "V5") (pinfunction "VSS_V5") (pintype "passive"))
      (node (ref "U1") (pin "W11") (pinfunction "VSS_W11") (pintype "passive"))
      (node (ref "U1") (pin "W2") (pinfunction "VSS_W2") (pintype "passive"))
      (node (ref "U1") (pin "W4") (pinfunction "VSS_W4") (pintype "passive"))
      (node (ref "U1") (pin "Y1") (pinfunction "VSS_Y1") (pintype "passive"))
      (node (ref "U1") (pin "Y12") (pinfunction "VSS_Y12") (pintype "passive"))
      (node (ref "U1") (pin "Y5") (pinfunction "VSS_Y5") (pintype "passive"))
      (node (ref "U1") (pin "Y8") (pinfunction "VSS_Y8") (pintype "passive"))
    )
    (net (code "63") (name "VCC1V8_LPDDR4_A") (class "Default")
      (node (ref "C37") (pin "2") (pinfunction "2_2") (pintype "passive"))
      (node (ref "C38") (pin "2") (pinfunction "2_2") (pintype "passive"))
      (node (ref "C39") (pin "2") (pinfunction "2_2") (pintype "passive"))
      (node (ref "C40") (pin "2") (pinfunction "2_2") (pintype "passive"))
      (node (ref "C41") (pin "2") (pinfunction "2_2") (pintype "passive"))
      (node (ref "C42") (pin "2") (pinfunction "2_2") (pintype "passive"))
      (node (ref "C43") (pin "2") (pinfunction "2_2") (pintype "passive"))
      (node (ref "C44") (pin "2") (pinfunction "2_2") (pintype "passive"))
      (node (ref "C45") (pin "2") (pinfunction "2_2") (pintype "passive"))
      (node (ref "FB1") (pin "2") (pinfunction "2_2") (pintype "passive"))
      (node (ref "U1") (pin "F1") (pinfunction "VDD1_F1") (pintype "passive"))
      (node (ref "U1") (pin "F12") (pinfunction "VDD1_F12") (pintype "passive"))
      (node (ref "U1") (pin "G4") (pinfunction "VDD1_G4") (pintype "passive"))
      (node (ref "U1") (pin "G9") (pinfunction "VDD1_G9") (pintype "passive"))
      (node (ref "U1") (pin "T4") (pinfunction "VDD1_T4") (pintype "passive"))
      (node (ref "U1") (pin "T9") (pinfunction "VDD1_T9") (pintype "passive"))
      (node (ref "U1") (pin "U1") (pinfunction "VDD1_U1") (pintype "passive"))
      (node (ref "U1") (pin "U12") (pinfunction "VDD1_U12") (pintype "passive"))
    )
    (net (code "64") (name "VCC_DDR") (class "Default")
      (node (ref "C1") (pin "2") (pinfunction "2_2") (pintype "passive"))
      (node (ref "C10") (pin "2") (pinfunction "2_2") (pintype "passive"))
      (node (ref "C19") (pin "2") (pinfunction "2_2") (pintype "passive"))
      (node (ref "C2") (pin "2") (pinfunction "2_2") (pintype "passive"))
      (node (ref "C20") (pin "2") (pinfunction "2_2") (pintype "passive"))
      (node (ref "C21") (pin "2") (pinfunction "2_2") (pintype "passive"))
      (node (ref "C22") (pin "2") (pinfunction "2_2") (pintype "passive"))
      (node (ref "C23") (pin "2") (pinfunction "2_2") (pintype "passive"))
      (node (ref "C24") (pin "2") (pinfunction "2_2") (pintype "passive"))
      (node (ref "C25") (pin "2") (pinfunction "2_2") (pintype "passive"))
      (node (ref "C26") (pin "2") (pinfunction "2_2") (pintype "passive"))
      (node (ref "C27") (pin "2") (pinfunction "2_2") (pintype "passive"))
      (node (ref "C3") (pin "2") (pinfunction "2_2") (pintype "passive"))
      (node (ref "C5") (pin "2") (pinfunction "2_2") (pintype "passive"))
      (node (ref "C6") (pin "2") (pinfunction "2_2") (pintype "passive"))
      (node (ref "C7") (pin "2") (pinfunction "2_2") (pintype "passive"))
      (node (ref "C8") (pin "2") (pinfunction "2_2") (pintype "passive"))
      (node (ref "C9") (pin "2") (pinfunction "2_2") (pintype "passive"))
      (node (ref "FB1") (pin "1") (pinfunction "1_1") (pintype "passive"))
      (node (ref "U1") (pin "A4") (pinfunction "VDD2_A4") (pintype "passive"))
      (node (ref "U1") (pin "A9") (pinfunction "VDD2_A9") (pintype "passive"))
      (node (ref "U1") (pin "AB4") (pinfunction "VDD2_AB4") (pintype "passive"))
      (node (ref "U1") (pin "AB9") (pinfunction "VDD2_AB9") (pintype "passive"))
      (node (ref "U1") (pin "F5") (pinfunction "VDD2_F5") (pintype "passive"))
      (node (ref "U1") (pin "F8") (pinfunction "VDD2_F8") (pintype "passive"))
      (node (ref "U1") (pin "H1") (pinfunction "VDD2_H1") (pintype "passive"))
      (node (ref "U1") (pin "H12") (pinfunction "VDD2_H12") (pintype "passive"))
      (node (ref "U1") (pin "H5") (pinfunction "VDD2_H5") (pintype "passive"))
      (node (ref "U1") (pin "H8") (pinfunction "VDD2_H8") (pintype "passive"))
      (node (ref "U1") (pin "K1") (pinfunction "VDD2_K1") (pintype "passive"))
      (node (ref "U1") (pin "K10") (pinfunction "VDD2_K10") (pintype "passive"))
      (node (ref "U1") (pin "K12") (pinfunction "VDD2_K12") (pintype "passive"))
      (node (ref "U1") (pin "K3") (pinfunction "VDD2_K3") (pintype "passive"))
      (node (ref "U1") (pin "N1") (pinfunction "VDD2_N1") (pintype "passive"))
      (node (ref "U1") (pin "N10") (pinfunction "VDD2_N10") (pintype "passive"))
      (node (ref "U1") (pin "N12") (pinfunction "VDD2_N12") (pintype "passive"))
      (node (ref "U1") (pin "N3") (pinfunction "VDD2_N3") (pintype "passive"))
      (node (ref "U1") (pin "R1") (pinfunction "VDD2_R1") (pintype "passive"))
      (node (ref "U1") (pin "R12") (pinfunction "VDD2_R12") (pintype "passive"))
      (node (ref "U1") (pin "R5") (pinfunction "VDD2_R5") (pintype "passive"))
      (node (ref "U1") (pin "R8") (pinfunction "VDD2_R8") (pintype "passive"))
      (node (ref "U1") (pin "U5") (pinfunction "VDD2_U5") (pintype "passive"))
      (node (ref "U1") (pin "U8") (pinfunction "VDD2_U8") (pintype "passive"))
    )
    (net (code "65") (name "VCC_DDRC") (class "Default")
      (node (ref "C11") (pin "2") (pinfunction "2_2") (pintype "passive"))
      (node (ref "C12") (pin "2") (pinfunction "2_2") (pintype "passive"))
      (node (ref "C13") (pin "2") (pinfunction "2_2") (pintype "passive"))
      (node (ref "C14") (pin "2") (pinfunction "2_2") (pintype "passive"))
      (node (ref "C15") (pin "2") (pinfunction "2_2") (pintype "passive"))
      (node (ref "C16") (pin "2") (pinfunction "2_2") (pintype "passive"))
      (node (ref "C17") (pin "2") (pinfunction "2_2") (pintype "passive"))
      (node (ref "C18") (pin "2") (pinfunction "2_2") (pintype "passive"))
      (node (ref "C28") (pin "2") (pinfunction "2_2") (pintype "passive"))
      (node (ref "C29") (pin "2") (pinfunction "2_2") (pintype "passive"))
      (node (ref "C30") (pin "2") (pinfunction "2_2") (pintype "passive"))
      (node (ref "C31") (pin "2") (pinfunction "2_2") (pintype "passive"))
      (node (ref "C32") (pin "2") (pinfunction "2_2") (pintype "passive"))
      (node (ref "C33") (pin "2") (pinfunction "2_2") (pintype "passive"))
      (node (ref "C34") (pin "2") (pinfunction "2_2") (pintype "passive"))
      (node (ref "C35") (pin "2") (pinfunction "2_2") (pintype "passive"))
      (node (ref "C36") (pin "2") (pinfunction "2_2") (pintype "passive"))
      (node (ref "C4") (pin "2") (pinfunction "2_2") (pintype "passive"))
      (node (ref "R1") (pin "2") (pinfunction "2_2") (pintype "passive"))
      (node (ref "R3") (pin "2") (pinfunction "2_2") (pintype "passive"))
      (node (ref "R4") (pin "2") (pinfunction "2_2") (pintype "passive"))
      (node (ref "U1") (pin "AA10") (pinfunction "VDDQ_AA10") (pintype "passive"))
      (node (ref "U1") (pin "AA3") (pinfunction "VDDQ_AA3") (pintype "passive"))
      (node (ref "U1") (pin "AA5") (pinfunction "VDDQ_AA5") (pintype "passive"))
      (node (ref "U1") (pin "AA8") (pinfunction "VDDQ_AA8") (pintype "passive"))
      (node (ref "U1") (pin "B10") (pinfunction "VDDQ_B10") (pintype "passive"))
      (node (ref "U1") (pin "B3") (pinfunction "VDDQ_B3") (pintype "passive"))
      (node (ref "U1") (pin "B5") (pinfunction "VDDQ_B5") (pintype "passive"))
      (node (ref "U1") (pin "B8") (pinfunction "VDDQ_B8") (pintype "passive"))
      (node (ref "U1") (pin "D1") (pinfunction "VDDQ_D1") (pintype "passive"))
      (node (ref "U1") (pin "D12") (pinfunction "VDDQ_D12") (pintype "passive"))
      (node (ref "U1") (pin "D5") (pinfunction "VDDQ_D5") (pintype "passive"))
      (node (ref "U1") (pin "D8") (pinfunction "VDDQ_D8") (pintype "passive"))
      (node (ref "U1") (pin "F10") (pinfunction "VDDQ_F10") (pintype "passive"))
      (node (ref "U1") (pin "F3") (pinfunction "VDDQ_F3") (pintype "passive"))
      (node (ref "U1") (pin "U10") (pinfunction "VDDQ_U10") (pintype "passive"))
      (node (ref "U1") (pin "U3") (pinfunction "VDDQ_U3") (pintype "passive"))
      (node (ref "U1") (pin "W1") (pinfunction "VDDQ_W1") (pintype "passive"))
      (node (ref "U1") (pin "W12") (pinfunction "VDDQ_W12") (pintype "passive"))
      (node (ref "U1") (pin "W5") (pinfunction "VDDQ_W5") (pintype "passive"))
      (node (ref "U1") (pin "W8") (pinfunction "VDDQ_W8") (pintype "passive"))
    )
    (net (code "66") (name "unconnected-(U1A-CA3_A-PadH10)") (class "Default")
      (node (ref "U1") (pin "H10") (pinfunction "CA3_A_H10") (pintype "passive+no_connect"))
    )
    (net (code "67") (name "unconnected-(U1A-CA3_B-PadR10)") (class "Default")
      (node (ref "U1") (pin "R10") (pinfunction "CA3_B_R10") (pintype "passive+no_connect"))
    )
    (net (code "68") (name "unconnected-(U1A-DQ1_B-PadY2)") (class "Default")
      (node (ref "U1") (pin "Y2") (pinfunction "DQ1_B_Y2") (pintype "passive+no_connect"))
    )
    (net (code "69") (name "unconnected-(U1A-DQ3_B-PadU2)") (class "Default")
      (node (ref "U1") (pin "U2") (pinfunction "DQ3_B_U2") (pintype "passive+no_connect"))
    )
    (net (code "70") (name "unconnected-(U1A-RESET_n-PadT11)") (class "Default")
      (node (ref "U1") (pin "T11") (pinfunction "RESET_n_T11") (pintype "passive+no_connect"))
    )
    (net (code "71") (name "unconnected-(U1B-DNU1-PadA1)") (class "Default")
      (node (ref "U1") (pin "A1") (pinfunction "DNU1_A1") (pintype "passive+no_connect"))
    )
    (net (code "72") (name "unconnected-(U1B-DNU2-PadA2)") (class "Default")
      (node (ref "U1") (pin "A2") (pinfunction "DNU2_A2") (pintype "passive+no_connect"))
    )
    (net (code "73") (name "unconnected-(U1B-DNU3-PadA11)") (class "Default")
      (node (ref "U1") (pin "A11") (pinfunction "DNU3_A11") (pintype "passive+no_connect"))
    )
    (net (code "74") (name "unconnected-(U1B-DNU4-PadA12)") (class "Default")
      (node (ref "U1") (pin "A12") (pinfunction "DNU4_A12") (pintype "passive+no_connect"))
    )
    (net (code "75") (name "unconnected-(U1B-DNU5-PadB1)") (class "Default")
      (node (ref "U1") (pin "B1") (pinfunction "DNU5_B1") (pintype "passive+no_connect"))
    )
    (net (code "76") (name "unconnected-(U1B-DNU6-PadB12)") (class "Default")
      (node (ref "U1") (pin "B12") (pinfunction "DNU6_B12") (pintype "passive+no_connect"))
    )
    (net (code "77") (name "unconnected-(U1B-DNU7-PadAA1)") (class "Default")
      (node (ref "U1") (pin "AA1") (pinfunction "DNU7_AA1") (pintype "passive+no_connect"))
    )
    (net (code "78") (name "unconnected-(U1B-DNU8-PadAA12)") (class "Default")
      (node (ref "U1") (pin "AA12") (pinfunction "DNU8_AA12") (pintype "passive+no_connect"))
    )
    (net (code "79") (name "unconnected-(U1B-DNU9-PadAB1)") (class "Default")
      (node (ref "U1") (pin "AB1") (pinfunction "DNU9_AB1") (pintype "passive+no_connect"))
    )
    (net (code "80") (name "unconnected-(U1B-DNU10-PadAB2)") (class "Default")
      (node (ref "U1") (pin "AB2") (pinfunction "DNU10_AB2") (pintype "passive+no_connect"))
    )
    (net (code "81") (name "unconnected-(U1B-DNU11-PadAB11)") (class "Default")
      (node (ref "U1") (pin "AB11") (pinfunction "DNU11_AB11") (pintype "passive+no_connect"))
    )
    (net (code "82") (name "unconnected-(U1B-DNU12-PadAB12)") (class "Default")
      (node (ref "U1") (pin "AB12") (pinfunction "DNU12_AB12") (pintype "passive+no_connect"))
    )
    (net (code "83") (name "unconnected-(U1B-DNU13-PadK8)") (class "Default")
      (node (ref "U1") (pin "K8") (pinfunction "DNU13_K8") (pintype "passive+no_connect"))
    )
    (net (code "84") (name "unconnected-(U1B-DNU14-PadN5)") (class "Default")
      (node (ref "U1") (pin "N5") (pinfunction "DNU14_N5") (pintype "passive+no_connect"))
    )
    (net (code "85") (name "unconnected-(U1B-DNU15-PadK5)") (class "Default")
      (node (ref "U1") (pin "K5") (pinfunction "DNU15_K5") (pintype "passive+no_connect"))
    )
    (net (code "86") (name "unconnected-(U1B-DNU16-PadG11)") (class "Default")
      (node (ref "U1") (pin "G11") (pinfunction "DNU16_G11") (pintype "passive+no_connect"))
    )
    (net (code "87") (name "unconnected-(U1B-DNU17-PadN8)") (class "Default")
      (node (ref "U1") (pin "N8") (pinfunction "DNU17_N8") (pintype "passive+no_connect"))
    )
    (net (code "88") (name "unconnected-(U1B-VSS-PadD4)") (class "Default")
      (node (ref "U1") (pin "D4") (pinfunction "VSS_D4") (pintype "passive+no_connect"))
    )
    (net (code "89") (name "unconnected-(U1B-VSS-PadT5)") (class "Default")
      (node (ref "U1") (pin "T5") (pinfunction "VSS_T5") (pintype "passive+no_connect"))
    )
    (net (code "90") (name "unconnected-(U1B-VSS-PadV8)") (class "Default")
      (node (ref "U1") (pin "V8") (pinfunction "VSS_V8") (pintype "passive+no_connect"))
    )
    (net (code "91") (name "unconnected-(U1B-VSS-PadW9)") (class "Default")
      (node (ref "U1") (pin "W9") (pinfunction "VSS_W9") (pintype "passive+no_connect"))
    )
  )
)
